# ESP8266-12F_Board.net
KiCad netlist of a schematic drawn in Altium Designer
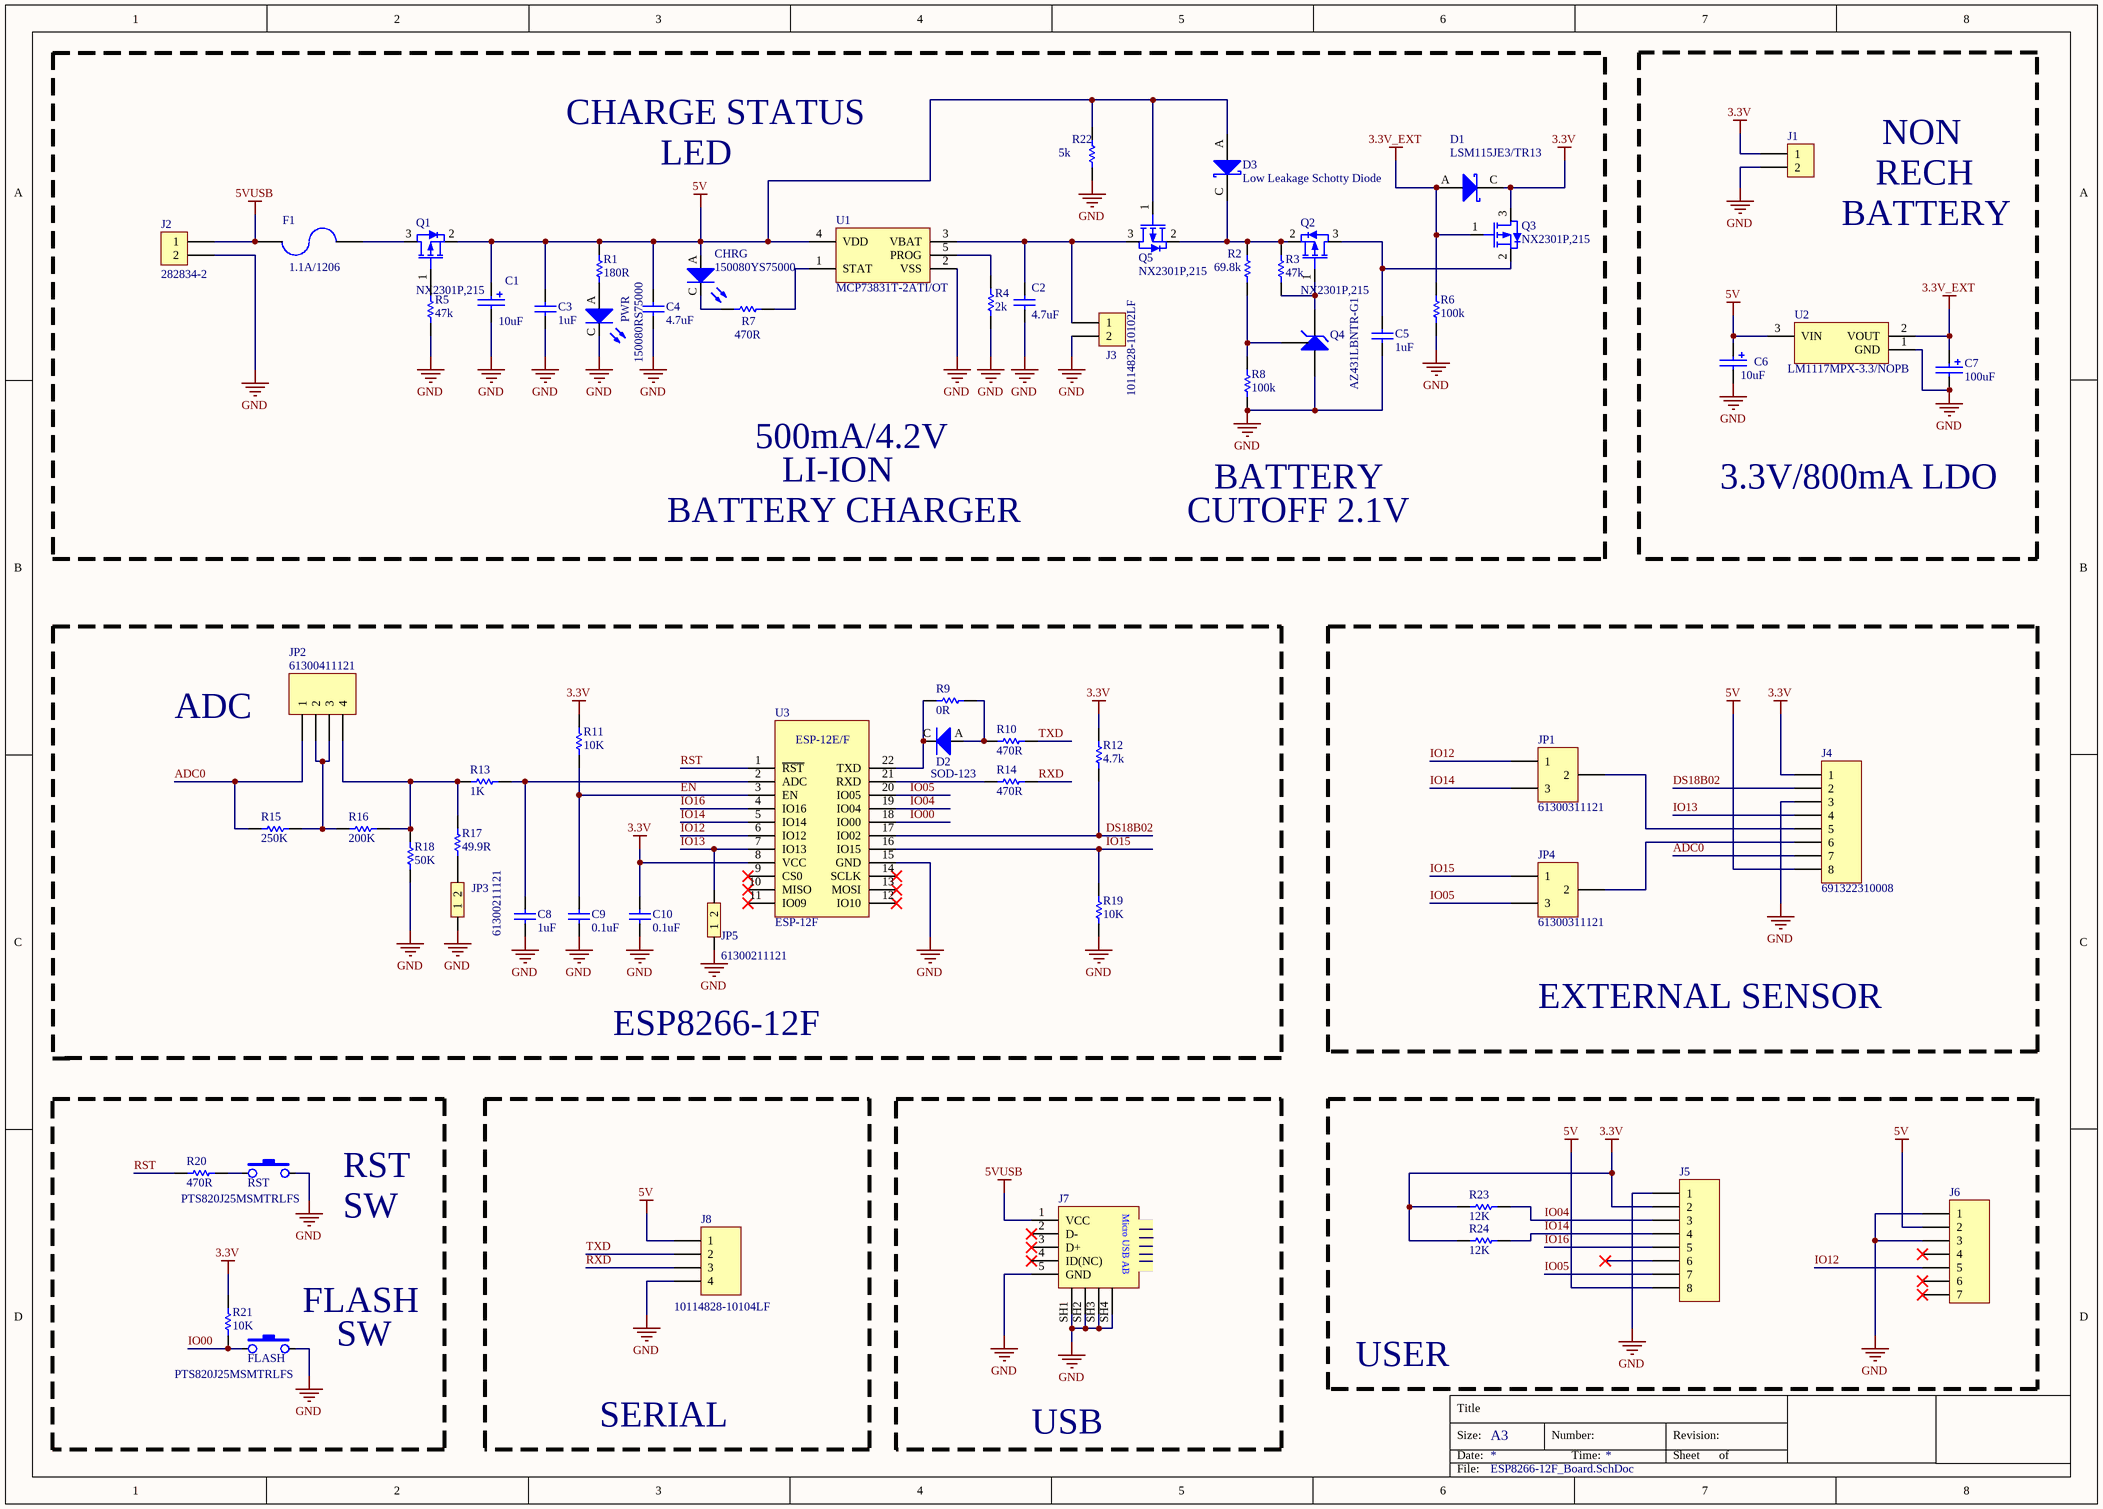
[diagram p0: ESP8266-12F_Board.SchDoc]

(export (version "E")
  (design (tool "Eeschema 10.0.6"))
  (components
    (comp (ref "C1")
      (value "10uF")
      (footprint "C1206+0805-Polar")
      (libsource (lib "M9J_RLC") (part "CAP_POLAR"))
    )
    (comp (ref "C2") (value "4.7uF") (footprint "C0603") (libsource (lib "M9J_RLC") (part "CAP_CERAMIC")))
    (comp (ref "C3") (value "1uF") (footprint "C0603") (libsource (lib "M9J_RLC") (part "CAP_CERAMIC")))
    (comp (ref "C4") (value "4.7uF") (footprint "C0603") (libsource (lib "M9J_RLC") (part "CAP_CERAMIC")))
    (comp (ref "C5") (value "1uF") (footprint "C0603") (libsource (lib "M9J_RLC") (part "CAP_CERAMIC")))
    (comp (ref "C6")
      (value "10uF")
      (footprint "C1206+0805-Polar")
      (libsource (lib "M9J_RLC") (part "CAP_POLAR"))
    )
    (comp (ref "C7")
      (value "100uF")
      (footprint "CAP_ALU_D6.3_H7.7")
      (libsource (lib "M9J_RLC") (part "CAP_POLAR"))
    )
    (comp (ref "C8") (value "1uF") (footprint "C0603") (libsource (lib "M9J_RLC") (part "CAP_CERAMIC")))
    (comp (ref "C9") (value "0.1uF") (footprint "C0603") (libsource (lib "M9J_RLC") (part "CAP_CERAMIC")))
    (comp (ref "C10") (value "0.1uF") (footprint "C0603") (libsource (lib "M9J_RLC") (part "CAP_CERAMIC")))
    (comp (ref "CHRG")
      (value "150080YS75000")
      (footprint "LED_0805_Red")
      (libsource (lib "M9J_Semiconductors") (part "LED"))
    )
    (comp (ref "D1")
      (value "LSM115JE3/TR13")
      (footprint "DO-214AC(SMA)")
      (libsource (lib "M9J_Semiconductors") (part "SCHOTTKY"))
    )
    (comp (ref "D2")
      (value "SOD-123")
      (footprint "SOD-123")
      (libsource (lib "M9J_Semiconductors") (part "DIODE"))
    )
    (comp (ref "D3")
      (value "Low Leakage Schotty Diode")
      (footprint "SOD-323")
      (libsource (lib "M9J_Semiconductors") (part "SCHOTTKY"))
    )
    (comp (ref "F1")
      (value "1.1A/1206")
      (footprint "FUSE_1206-(1206L300SLTHYR)")
      (libsource (lib "M9J_Misc") (part "FUSE-2PIN"))
    )
    (comp (ref "FLASH")
      (value "PTS820J25MSMTRLFS")
      (footprint "SPST-TACT-SMD-(PTS820J25MSMTRLFS)")
      (libsource (lib "M9J_Switches") (part "SPST-TACT"))
    )
    (comp (ref "J1")
      (value "B2B-XH-A(LF)(SN)")
      (footprint "HDR1X2-P2.5-JST-(B2B-XH-A(LF)(SN))")
      (libsource (lib "M9J_Connectors") (part "HDR1X2"))
    )
    (comp (ref "J2")
      (value "282834-2")
      (footprint "TB1X2_P2.54-(282834-2)")
      (libsource (lib "") (part "HDR1X2_1"))
    )
    (comp (ref "J3")
      (value "10114828-10102LF")
      (footprint "HDR1X2_SMD_P1.25-(10114828-10102LF)")
      (libsource (lib "M9J_Connectors") (part "HDR1X2"))
    )
    (comp (ref "J4")
      (value "691322310008")
      (footprint "TB-RA-1X8-(691322310008)")
      (libsource (lib "M9J_Connectors") (part "HDR1X8"))
    )
    (comp (ref "J5")
      (value "75915-308LF")
      (footprint "HDR1X8_FEMALE-(75915-308LF)")
      (libsource (lib "M9J_Connectors") (part "HDR1X8"))
    )
    (comp (ref "J6")
      (value "0901471107")
      (footprint "HDR1X7_FEMALE-(0901471107)")
      (libsource (lib "M9J_Connectors") (part "HDR1X7"))
    )
    (comp (ref "J7")
      (value "USB-MICRO")
      (footprint "USB_MICRO_SMD-2")
      (libsource (lib "M9J_Connectors") (part "USB-MICRO"))
    )
    (comp (ref "J8")
      (value "10114828-10104LF")
      (footprint "HDR1X4_SMD_P1.25-(10114828-10104LF)")
      (libsource (lib "M9J_Connectors") (part "HDR1X4"))
    )
    (comp (ref "JP1")
      (value "61300311121")
      (footprint "HDR1X3_MALE-(61300311121)")
      (libsource (lib "M9J_Connectors") (part "JUMPER_3PIN"))
    )
    (comp (ref "JP2")
      (value "61300411121")
      (footprint "HDR1X4_MALE-(61300411121)")
      (libsource (lib "") (part "HDR1X4_1"))
    )
    (comp (ref "JP3")
      (value "61300211121")
      (footprint "HDR1X2_MALE-(61300211121)")
      (libsource (lib "M9J_Connectors") (part "JUMPER-2PIN"))
    )
    (comp (ref "JP4")
      (value "61300311121")
      (footprint "HDR1X3_MALE-(61300311121)")
      (libsource (lib "M9J_Connectors") (part "JUMPER_3PIN"))
    )
    (comp (ref "JP5")
      (value "61300211121")
      (footprint "HDR1X2_MALE-(61300211121)")
      (libsource (lib "M9J_Connectors") (part "JUMPER-2PIN"))
    )
    (comp (ref "PWR")
      (value "150080RS75000")
      (footprint "LED_0805_Red")
      (libsource (lib "M9J_Semiconductors") (part "LED"))
    )
    (comp (ref "Q1")
      (value "NX2301P,215")
      (footprint "SOT23-3")
      (libsource (lib "M9J_Semiconductors") (part "PMOS"))
    )
    (comp (ref "Q2")
      (value "NX2301P,215")
      (footprint "SOT23-3")
      (libsource (lib "M9J_Semiconductors") (part "PMOS"))
    )
    (comp (ref "Q3")
      (value "NX2301P,215")
      (footprint "SOT23-3")
      (libsource (lib "M9J_Semiconductors") (part "PMOS"))
    )
    (comp (ref "Q4")
      (value "AZ431LBNTR-G1")
      (footprint "SOT23-3")
      (libsource (lib "M9J_Semiconductors") (part "AZ431LBNTR-G1"))
    )
    (comp (ref "Q5")
      (value "NX2301P,215")
      (footprint "SOT23-3")
      (libsource (lib "ESP8266-12F_Board_V1R1") (part "PMOS"))
    )
    (comp (ref "R1") (value "180R") (footprint "R0603") (libsource (lib "M9J_RLC") (part "RES")))
    (comp (ref "R2") (value "69.8k") (footprint "R0603") (libsource (lib "M9J_RLC") (part "RES")))
    (comp (ref "R3") (value "47k") (footprint "R0603") (libsource (lib "M9J_RLC") (part "RES")))
    (comp (ref "R4") (value "2k") (footprint "R0603") (libsource (lib "M9J_RLC") (part "RES")))
    (comp (ref "R5") (value "47k") (footprint "R0603") (libsource (lib "M9J_RLC") (part "RES")))
    (comp (ref "R6") (value "100k") (footprint "R0603") (libsource (lib "M9J_RLC") (part "RES")))
    (comp (ref "R7") (value "470R") (footprint "R0603") (libsource (lib "M9J_RLC") (part "RES")))
    (comp (ref "R8") (value "100k") (footprint "R0603") (libsource (lib "M9J_RLC") (part "RES")))
    (comp (ref "R9") (value "0R") (footprint "R0603") (libsource (lib "M9J_RLC") (part "RES")))
    (comp (ref "R10") (value "470R") (footprint "R0603") (libsource (lib "M9J_RLC") (part "RES")))
    (comp (ref "R11") (value "10K") (footprint "R0603") (libsource (lib "M9J_RLC") (part "RES")))
    (comp (ref "R12") (value "4.7k") (footprint "R0603") (libsource (lib "M9J_RLC") (part "RES")))
    (comp (ref "R13") (value "1K") (footprint "R0603") (libsource (lib "M9J_RLC") (part "RES")))
    (comp (ref "R14") (value "470R") (footprint "R0603") (libsource (lib "M9J_RLC") (part "RES")))
    (comp (ref "R15") (value "250K") (footprint "R0603") (libsource (lib "M9J_RLC") (part "RES")))
    (comp (ref "R16") (value "200K") (footprint "R0603") (libsource (lib "M9J_RLC") (part "RES")))
    (comp (ref "R17") (value "49.9R") (footprint "R0603") (libsource (lib "M9J_RLC") (part "RES")))
    (comp (ref "R18") (value "50K") (footprint "R0603") (libsource (lib "M9J_RLC") (part "RES")))
    (comp (ref "R19") (value "10K") (footprint "R0603") (libsource (lib "M9J_RLC") (part "RES")))
    (comp (ref "R20") (value "470R") (footprint "R0603") (libsource (lib "M9J_RLC") (part "RES")))
    (comp (ref "R21") (value "10K") (footprint "R0603") (libsource (lib "M9J_RLC") (part "RES")))
    (comp (ref "R22")
      (value "5k")
      (footprint "R0603")
      (libsource (lib "ESP8266-12F_Board_V1R1") (part "RES"))
    )
    (comp (ref "R23") (value "12K") (footprint "R0603") (libsource (lib "M9J_RLC") (part "RES")))
    (comp (ref "R24") (value "12K") (footprint "R0603") (libsource (lib "M9J_RLC") (part "RES")))
    (comp (ref "RST")
      (value "PTS820J25MSMTRLFS")
      (footprint "SPST-TACT-SMD-(PTS820J25MSMTRLFS)")
      (libsource (lib "M9J_Switches") (part "SPST-TACT"))
    )
    (comp (ref "U1")
      (value "MCP73831T-2ATI/OT")
      (footprint "SOT23-5")
      (libsource (lib "M9J_PowerICs") (part "MCP73831T-2ATI/OT"))
    )
    (comp (ref "U2")
      (value "LM1117MPX-3.3/NOPB")
      (footprint "SOT-223-4")
      (libsource (lib "M9J_PowerICs") (part "LM1117MPX-3.3/NOPB"))
    )
    (comp (ref "U3")
      (value "ESP-12F")
      (footprint "ESP_12E/F")
      (description "Class 2 embedded Bluetooth 4.0 module")
      (libsource (lib "M9J_RF") (part "ESP-12E/F"))
    )
  )
  (nets
    (net (code "2") (name "/ADC0") (class "Default")
      (node (ref "J4") (pin "7") (pinfunction "7_7") (pintype "passive"))
      (node (ref "JP2") (pin "1") (pinfunction "1_1") (pintype "passive"))
      (node (ref "R15") (pin "2") (pinfunction "2_2") (pintype "passive"))
    )
    (net (code "3") (name "/DS18B02") (class "Default")
      (node (ref "J4") (pin "2") (pinfunction "2_2") (pintype "passive"))
      (node (ref "R12") (pin "2") (pinfunction "2_2") (pintype "passive"))
      (node (ref "U3") (pin "17") (pinfunction "IO02_17") (pintype "passive"))
    )
    (net (code "4") (name "/EN") (class "Default")
      (node (ref "C9") (pin "2") (pinfunction "2_2") (pintype "passive"))
      (node (ref "R11") (pin "1") (pinfunction "1_1") (pintype "passive"))
      (node (ref "U3") (pin "3") (pinfunction "EN_3") (pintype "passive"))
    )
    (net (code "5") (name "/IO00") (class "Default")
      (node (ref "FLASH") (pin "1") (pinfunction "1_1") (pintype "passive"))
      (node (ref "R21") (pin "2") (pinfunction "2_2") (pintype "passive"))
      (node (ref "U3") (pin "18") (pinfunction "IO00_18") (pintype "passive"))
    )
    (net (code "6") (name "/IO04") (class "Default")
      (node (ref "J5") (pin "3") (pinfunction "3_3") (pintype "passive"))
      (node (ref "R23") (pin "1") (pinfunction "1_1") (pintype "passive"))
      (node (ref "U3") (pin "19") (pinfunction "IO04_19") (pintype "passive"))
    )
    (net (code "7") (name "/IO05") (class "Default")
      (node (ref "J5") (pin "7") (pinfunction "7_7") (pintype "passive"))
      (node (ref "JP4") (pin "3") (pinfunction "3_3") (pintype "passive"))
      (node (ref "U3") (pin "20") (pinfunction "IO05_20") (pintype "passive"))
    )
    (net (code "8") (name "/IO12") (class "Default")
      (node (ref "J6") (pin "5") (pinfunction "5_5") (pintype "passive"))
      (node (ref "JP1") (pin "1") (pinfunction "1_1") (pintype "passive"))
      (node (ref "U3") (pin "6") (pinfunction "IO12_6") (pintype "passive"))
    )
    (net (code "9") (name "/IO13") (class "Default")
      (node (ref "J4") (pin "4") (pinfunction "4_4") (pintype "passive"))
      (node (ref "JP5") (pin "2") (pinfunction "2_2") (pintype "passive"))
      (node (ref "U3") (pin "7") (pinfunction "IO13_7") (pintype "passive"))
    )
    (net (code "10") (name "/IO14") (class "Default")
      (node (ref "J5") (pin "4") (pinfunction "4_4") (pintype "passive"))
      (node (ref "JP1") (pin "3") (pinfunction "3_3") (pintype "passive"))
      (node (ref "R24") (pin "1") (pinfunction "1_1") (pintype "passive"))
      (node (ref "U3") (pin "5") (pinfunction "IO14_5") (pintype "passive"))
    )
    (net (code "11") (name "/IO15") (class "Default")
      (node (ref "JP4") (pin "1") (pinfunction "1_1") (pintype "passive"))
      (node (ref "R19") (pin "1") (pinfunction "1_1") (pintype "passive"))
      (node (ref "U3") (pin "16") (pinfunction "IO15_16") (pintype "passive"))
    )
    (net (code "12") (name "/IO16") (class "Default")
      (node (ref "J5") (pin "5") (pinfunction "5_5") (pintype "passive"))
      (node (ref "U3") (pin "4") (pinfunction "IO16_4") (pintype "passive"))
    )
    (net (code "13") (name "/RST") (class "Default")
      (node (ref "R20") (pin "2") (pinfunction "2_2") (pintype "passive"))
      (node (ref "U3") (pin "1") (pinfunction "~{RST}_1") (pintype "passive"))
    )
    (net (code "14") (name "/RXD") (class "Default")
      (node (ref "J8") (pin "3") (pinfunction "3_3") (pintype "passive"))
      (node (ref "R14") (pin "1") (pinfunction "1_1") (pintype "passive"))
    )
    (net (code "15") (name "/TXD") (class "Default")
      (node (ref "J8") (pin "2") (pinfunction "2_2") (pintype "passive"))
      (node (ref "R10") (pin "1") (pinfunction "1_1") (pintype "passive"))
    )
    (net (code "16") (name "3.3V") (class "Default")
      (node (ref "C10") (pin "2") (pinfunction "2_2") (pintype "passive"))
      (node (ref "D1") (pin "C") (pinfunction "C_C") (pintype "passive"))
      (node (ref "J1") (pin "1") (pinfunction "1_1") (pintype "passive"))
      (node (ref "J4") (pin "1") (pinfunction "1_1") (pintype "passive"))
      (node (ref "J5") (pin "2") (pinfunction "2_2") (pintype "passive"))
      (node (ref "Q3") (pin "3") (pinfunction "D_3") (pintype "passive"))
      (node (ref "R11") (pin "2") (pinfunction "2_2") (pintype "passive"))
      (node (ref "R12") (pin "1") (pinfunction "1_1") (pintype "passive"))
      (node (ref "R21") (pin "1") (pinfunction "1_1") (pintype "passive"))
      (node (ref "R23") (pin "2") (pinfunction "2_2") (pintype "passive"))
      (node (ref "R24") (pin "2") (pinfunction "2_2") (pintype "passive"))
      (node (ref "U3") (pin "8") (pinfunction "VCC_8") (pintype "passive"))
    )
    (net (code "17") (name "3.3V_EXT") (class "Default")
      (node (ref "C7") (pin "1") (pinfunction "1_1") (pintype "passive"))
      (node (ref "D1") (pin "A") (pinfunction "A_A") (pintype "passive"))
      (node (ref "Q3") (pin "1") (pinfunction "G_1") (pintype "passive"))
      (node (ref "R6") (pin "1") (pinfunction "1_1") (pintype "passive"))
      (node (ref "U2") (pin "2") (pinfunction "VOUT_2") (pintype "passive"))
    )
    (net (code "18") (name "5V") (class "Default")
      (node (ref "C1") (pin "1") (pinfunction "1_1") (pintype "passive"))
      (node (ref "C3") (pin "2") (pinfunction "2_2") (pintype "passive"))
      (node (ref "C4") (pin "2") (pinfunction "2_2") (pintype "passive"))
      (node (ref "C6") (pin "1") (pinfunction "1_1") (pintype "passive"))
      (node (ref "CHRG") (pin "A") (pinfunction "A_A") (pintype "passive"))
      (node (ref "D3") (pin "A") (pinfunction "A_A") (pintype "passive"))
      (node (ref "J4") (pin "8") (pinfunction "8_8") (pintype "passive"))
      (node (ref "J5") (pin "8") (pinfunction "8_8") (pintype "passive"))
      (node (ref "J6") (pin "2") (pinfunction "2_2") (pintype "passive"))
      (node (ref "J8") (pin "1") (pinfunction "1_1") (pintype "passive"))
      (node (ref "Q1") (pin "2") (pinfunction "S_2") (pintype "passive"))
      (node (ref "Q5") (pin "1") (pinfunction "G_1") (pintype "passive"))
      (node (ref "R1") (pin "2") (pinfunction "2_2") (pintype "passive"))
      (node (ref "R22") (pin "1") (pinfunction "1_1") (pintype "passive"))
      (node (ref "U1") (pin "4") (pinfunction "VDD_4") (pintype "passive"))
      (node (ref "U2") (pin "3") (pinfunction "VIN_3") (pintype "passive"))
    )
    (net (code "19") (name "5VUSB") (class "Default")
      (node (ref "F1") (pin "1") (pinfunction "1_1") (pintype "passive"))
      (node (ref "J2") (pin "1") (pinfunction "1_1") (pintype "passive"))
      (node (ref "J7") (pin "1") (pinfunction "VCC_1") (pintype "passive"))
    )
    (net (code "20") (name "GND") (class "Default")
      (node (ref "C1") (pin "2") (pinfunction "2_2") (pintype "passive"))
      (node (ref "C10") (pin "1") (pinfunction "1_1") (pintype "passive"))
      (node (ref "C2") (pin "1") (pinfunction "1_1") (pintype "passive"))
      (node (ref "C3") (pin "1") (pinfunction "1_1") (pintype "passive"))
      (node (ref "C4") (pin "1") (pinfunction "1_1") (pintype "passive"))
      (node (ref "C5") (pin "1") (pinfunction "1_1") (pintype "passive"))
      (node (ref "C6") (pin "2") (pinfunction "2_2") (pintype "passive"))
      (node (ref "C7") (pin "2") (pinfunction "2_2") (pintype "passive"))
      (node (ref "C8") (pin "1") (pinfunction "1_1") (pintype "passive"))
      (node (ref "C9") (pin "1") (pinfunction "1_1") (pintype "passive"))
      (node (ref "FLASH") (pin "2") (pinfunction "2_2") (pintype "passive"))
      (node (ref "J1") (pin "2") (pinfunction "2_2") (pintype "passive"))
      (node (ref "J2") (pin "2") (pinfunction "2_2") (pintype "passive"))
      (node (ref "J3") (pin "2") (pinfunction "2_2") (pintype "passive"))
      (node (ref "J4") (pin "3") (pinfunction "3_3") (pintype "passive"))
      (node (ref "J5") (pin "1") (pinfunction "1_1") (pintype "passive"))
      (node (ref "J6") (pin "1") (pinfunction "1_1") (pintype "passive"))
      (node (ref "J6") (pin "3") (pinfunction "3_3") (pintype "passive"))
      (node (ref "J7") (pin "5") (pinfunction "GND_5") (pintype "passive"))
      (node (ref "J7") (pin "SH1") (pinfunction "6_SH1") (pintype "passive"))
      (node (ref "J7") (pin "SH2") (pinfunction "7_SH2") (pintype "passive"))
      (node (ref "J7") (pin "SH3") (pinfunction "8_SH3") (pintype "passive"))
      (node (ref "J7") (pin "SH4") (pinfunction "9_SH4") (pintype "passive"))
      (node (ref "J8") (pin "4") (pinfunction "4_4") (pintype "passive"))
      (node (ref "JP3") (pin "1") (pinfunction "1_1") (pintype "passive"))
      (node (ref "JP5") (pin "1") (pinfunction "1_1") (pintype "passive"))
      (node (ref "PWR") (pin "C") (pinfunction "C_C") (pintype "passive"))
      (node (ref "Q4") (pin "3") (pinfunction "A_3") (pintype "passive"))
      (node (ref "R18") (pin "1") (pinfunction "1_1") (pintype "passive"))
      (node (ref "R19") (pin "2") (pinfunction "2_2") (pintype "passive"))
      (node (ref "R22") (pin "2") (pinfunction "2_2") (pintype "passive"))
      (node (ref "R4") (pin "2") (pinfunction "2_2") (pintype "passive"))
      (node (ref "R5") (pin "1") (pinfunction "1_1") (pintype "passive"))
      (node (ref "R6") (pin "2") (pinfunction "2_2") (pintype "passive"))
      (node (ref "R8") (pin "2") (pinfunction "2_2") (pintype "passive"))
      (node (ref "RST") (pin "2") (pinfunction "2_2") (pintype "passive"))
      (node (ref "U1") (pin "2") (pinfunction "VSS_2") (pintype "passive"))
      (node (ref "U2") (pin "1") (pinfunction "GND_1") (pintype "passive"))
      (node (ref "U3") (pin "15") (pinfunction "GND_15") (pintype "passive"))
    )
    (net (code "21") (name "Net-(CHRG-PadC)") (class "Default")
      (node (ref "CHRG") (pin "C") (pinfunction "C_C") (pintype "passive"))
      (node (ref "R7") (pin "2") (pinfunction "2_2") (pintype "passive"))
    )
    (net (code "22") (name "Net-(D2-PadA)") (class "Default")
      (node (ref "D2") (pin "A") (pinfunction "A_A") (pintype "passive"))
      (node (ref "R10") (pin "2") (pinfunction "2_2") (pintype "passive"))
      (node (ref "R9") (pin "1") (pinfunction "1_1") (pintype "passive"))
    )
    (net (code "23") (name "Net-(J4-Pad5)") (class "Default")
      (node (ref "J4") (pin "5") (pinfunction "5_5") (pintype "passive"))
      (node (ref "JP1") (pin "2") (pinfunction "2_2") (pintype "passive"))
    )
    (net (code "24") (name "Net-(J4-Pad6)") (class "Default")
      (node (ref "J4") (pin "6") (pinfunction "6_6") (pintype "passive"))
      (node (ref "JP4") (pin "2") (pinfunction "2_2") (pintype "passive"))
    )
    (net (code "25") (name "Net-(JP2-Pad2)") (class "Default")
      (node (ref "JP2") (pin "2") (pinfunction "2_2") (pintype "passive"))
      (node (ref "JP2") (pin "3") (pinfunction "3_3") (pintype "passive"))
      (node (ref "R15") (pin "1") (pinfunction "1_1") (pintype "passive"))
      (node (ref "R16") (pin "2") (pinfunction "2_2") (pintype "passive"))
    )
    (net (code "26") (name "Net-(JP2-Pad4)") (class "Default")
      (node (ref "JP2") (pin "4") (pinfunction "4_4") (pintype "passive"))
      (node (ref "R13") (pin "1") (pinfunction "1_1") (pintype "passive"))
      (node (ref "R16") (pin "1") (pinfunction "1_1") (pintype "passive"))
      (node (ref "R17") (pin "1") (pinfunction "1_1") (pintype "passive"))
      (node (ref "R18") (pin "2") (pinfunction "2_2") (pintype "passive"))
    )
    (net (code "27") (name "Net-(JP3-Pad2)") (class "Default")
      (node (ref "JP3") (pin "2") (pinfunction "2_2") (pintype "passive"))
      (node (ref "R17") (pin "2") (pinfunction "2_2") (pintype "passive"))
    )
    (net (code "28") (name "Net-(PWR-PadA)") (class "Default")
      (node (ref "PWR") (pin "A") (pinfunction "A_A") (pintype "passive"))
      (node (ref "R1") (pin "1") (pinfunction "1_1") (pintype "passive"))
    )
    (net (code "29") (name "Net-(Q1-D)") (class "Default")
      (node (ref "F1") (pin "2") (pinfunction "2_2") (pintype "passive"))
      (node (ref "Q1") (pin "3") (pinfunction "D_3") (pintype "passive"))
    )
    (net (code "30") (name "Net-(Q1-G)") (class "Default")
      (node (ref "Q1") (pin "1") (pinfunction "G_1") (pintype "passive"))
      (node (ref "R5") (pin "2") (pinfunction "2_2") (pintype "passive"))
    )
    (net (code "31") (name "Net-(Q2-D)") (class "Default")
      (node (ref "C5") (pin "2") (pinfunction "2_2") (pintype "passive"))
      (node (ref "Q2") (pin "3") (pinfunction "D_3") (pintype "passive"))
      (node (ref "Q3") (pin "2") (pinfunction "S_2") (pintype "passive"))
    )
    (net (code "32") (name "Net-(Q2-G)") (class "Default")
      (node (ref "Q2") (pin "1") (pinfunction "G_1") (pintype "passive"))
      (node (ref "Q4") (pin "2") (pinfunction "C_2") (pintype "passive"))
      (node (ref "R3") (pin "2") (pinfunction "2_2") (pintype "passive"))
    )
    (net (code "33") (name "Net-(Q2-S)") (class "Default")
      (node (ref "D3") (pin "C") (pinfunction "C_C") (pintype "passive"))
      (node (ref "Q2") (pin "2") (pinfunction "S_2") (pintype "passive"))
      (node (ref "Q5") (pin "2") (pinfunction "S_2") (pintype "passive"))
      (node (ref "R2") (pin "1") (pinfunction "1_1") (pintype "passive"))
      (node (ref "R3") (pin "1") (pinfunction "1_1") (pintype "passive"))
    )
    (net (code "34") (name "Net-(Q4-REF)") (class "Default")
      (node (ref "Q4") (pin "1") (pinfunction "REF_1") (pintype "passive"))
      (node (ref "R2") (pin "2") (pinfunction "2_2") (pintype "passive"))
      (node (ref "R8") (pin "1") (pinfunction "1_1") (pintype "passive"))
    )
    (net (code "35") (name "Net-(Q5-D)") (class "Default")
      (node (ref "C2") (pin "2") (pinfunction "2_2") (pintype "passive"))
      (node (ref "J3") (pin "1") (pinfunction "1_1") (pintype "passive"))
      (node (ref "Q5") (pin "3") (pinfunction "D_3") (pintype "passive"))
      (node (ref "U1") (pin "3") (pinfunction "VBAT_3") (pintype "passive"))
    )
    (net (code "36") (name "Net-(R20-Pad1)") (class "Default")
      (node (ref "R20") (pin "1") (pinfunction "1_1") (pintype "passive"))
      (node (ref "RST") (pin "1") (pinfunction "1_1") (pintype "passive"))
    )
    (net (code "37") (name "Net-(U1-PROG)") (class "Default")
      (node (ref "R4") (pin "1") (pinfunction "1_1") (pintype "passive"))
      (node (ref "U1") (pin "5") (pinfunction "PROG_5") (pintype "passive"))
    )
    (net (code "38") (name "Net-(U1-STAT)") (class "Default")
      (node (ref "R7") (pin "1") (pinfunction "1_1") (pintype "passive"))
      (node (ref "U1") (pin "1") (pinfunction "STAT_1") (pintype "passive"))
    )
    (net (code "39") (name "Net-(U3-ADC)") (class "Default")
      (node (ref "C8") (pin "2") (pinfunction "2_2") (pintype "passive"))
      (node (ref "R13") (pin "2") (pinfunction "2_2") (pintype "passive"))
      (node (ref "U3") (pin "2") (pinfunction "ADC_2") (pintype "passive"))
    )
    (net (code "40") (name "Net-(U3-RXD)") (class "Default")
      (node (ref "R14") (pin "2") (pinfunction "2_2") (pintype "passive"))
      (node (ref "U3") (pin "21") (pinfunction "RXD_21") (pintype "passive"))
    )
    (net (code "41") (name "Net-(U3-TXD)") (class "Default")
      (node (ref "D2") (pin "C") (pinfunction "C_C") (pintype "passive"))
      (node (ref "R9") (pin "2") (pinfunction "2_2") (pintype "passive"))
      (node (ref "U3") (pin "22") (pinfunction "TXD_22") (pintype "passive"))
    )
    (net (code "42") (name "unconnected-(J5-Pad6)") (class "Default")
      (node (ref "J5") (pin "6") (pinfunction "6_6") (pintype "passive+no_connect"))
    )
    (net (code "43") (name "unconnected-(J6-Pad4)") (class "Default")
      (node (ref "J6") (pin "4") (pinfunction "4_4") (pintype "passive+no_connect"))
    )
    (net (code "44") (name "unconnected-(J6-Pad6)") (class "Default")
      (node (ref "J6") (pin "6") (pinfunction "6_6") (pintype "passive+no_connect"))
    )
    (net (code "45") (name "unconnected-(J6-Pad7)") (class "Default")
      (node (ref "J6") (pin "7") (pinfunction "7_7") (pintype "passive+no_connect"))
    )
    (net (code "46") (name "unconnected-(J7-D+-Pad3)") (class "Default")
      (node (ref "J7") (pin "3") (pinfunction "D+_3") (pintype "passive+no_connect"))
    )
    (net (code "47") (name "unconnected-(J7-D--Pad2)") (class "Default")
      (node (ref "J7") (pin "2") (pinfunction "D-_2") (pintype "passive+no_connect"))
    )
    (net (code "48") (name "unconnected-(J7-ID(NC)-Pad4)") (class "Default")
      (node (ref "J7") (pin "4") (pinfunction "ID(NC)_4") (pintype "passive+no_connect"))
    )
    (net (code "49") (name "unconnected-(U3-CS0-Pad9)") (class "Default")
      (node (ref "U3") (pin "9") (pinfunction "CS0_9") (pintype "passive+no_connect"))
    )
    (net (code "50") (name "unconnected-(U3-IO09-Pad11)") (class "Default")
      (node (ref "U3") (pin "11") (pinfunction "IO09_11") (pintype "passive+no_connect"))
    )
    (net (code "51") (name "unconnected-(U3-IO10-Pad12)") (class "Default")
      (node (ref "U3") (pin "12") (pinfunction "IO10_12") (pintype "passive+no_connect"))
    )
    (net (code "52") (name "unconnected-(U3-MISO-Pad10)") (class "Default")
      (node (ref "U3") (pin "10") (pinfunction "MISO_10") (pintype "passive+no_connect"))
    )
    (net (code "53") (name "unconnected-(U3-MOSI-Pad13)") (class "Default")
      (node (ref "U3") (pin "13") (pinfunction "MOSI_13") (pintype "passive+no_connect"))
    )
    (net (code "54") (name "unconnected-(U3-SCLK-Pad14)") (class "Default")
      (node (ref "U3") (pin "14") (pinfunction "SCLK_14") (pintype "passive+no_connect"))
    )
  )
)
